# PWM_Controller_SG3525.net
KiCad netlist of a schematic drawn in Altium Designer
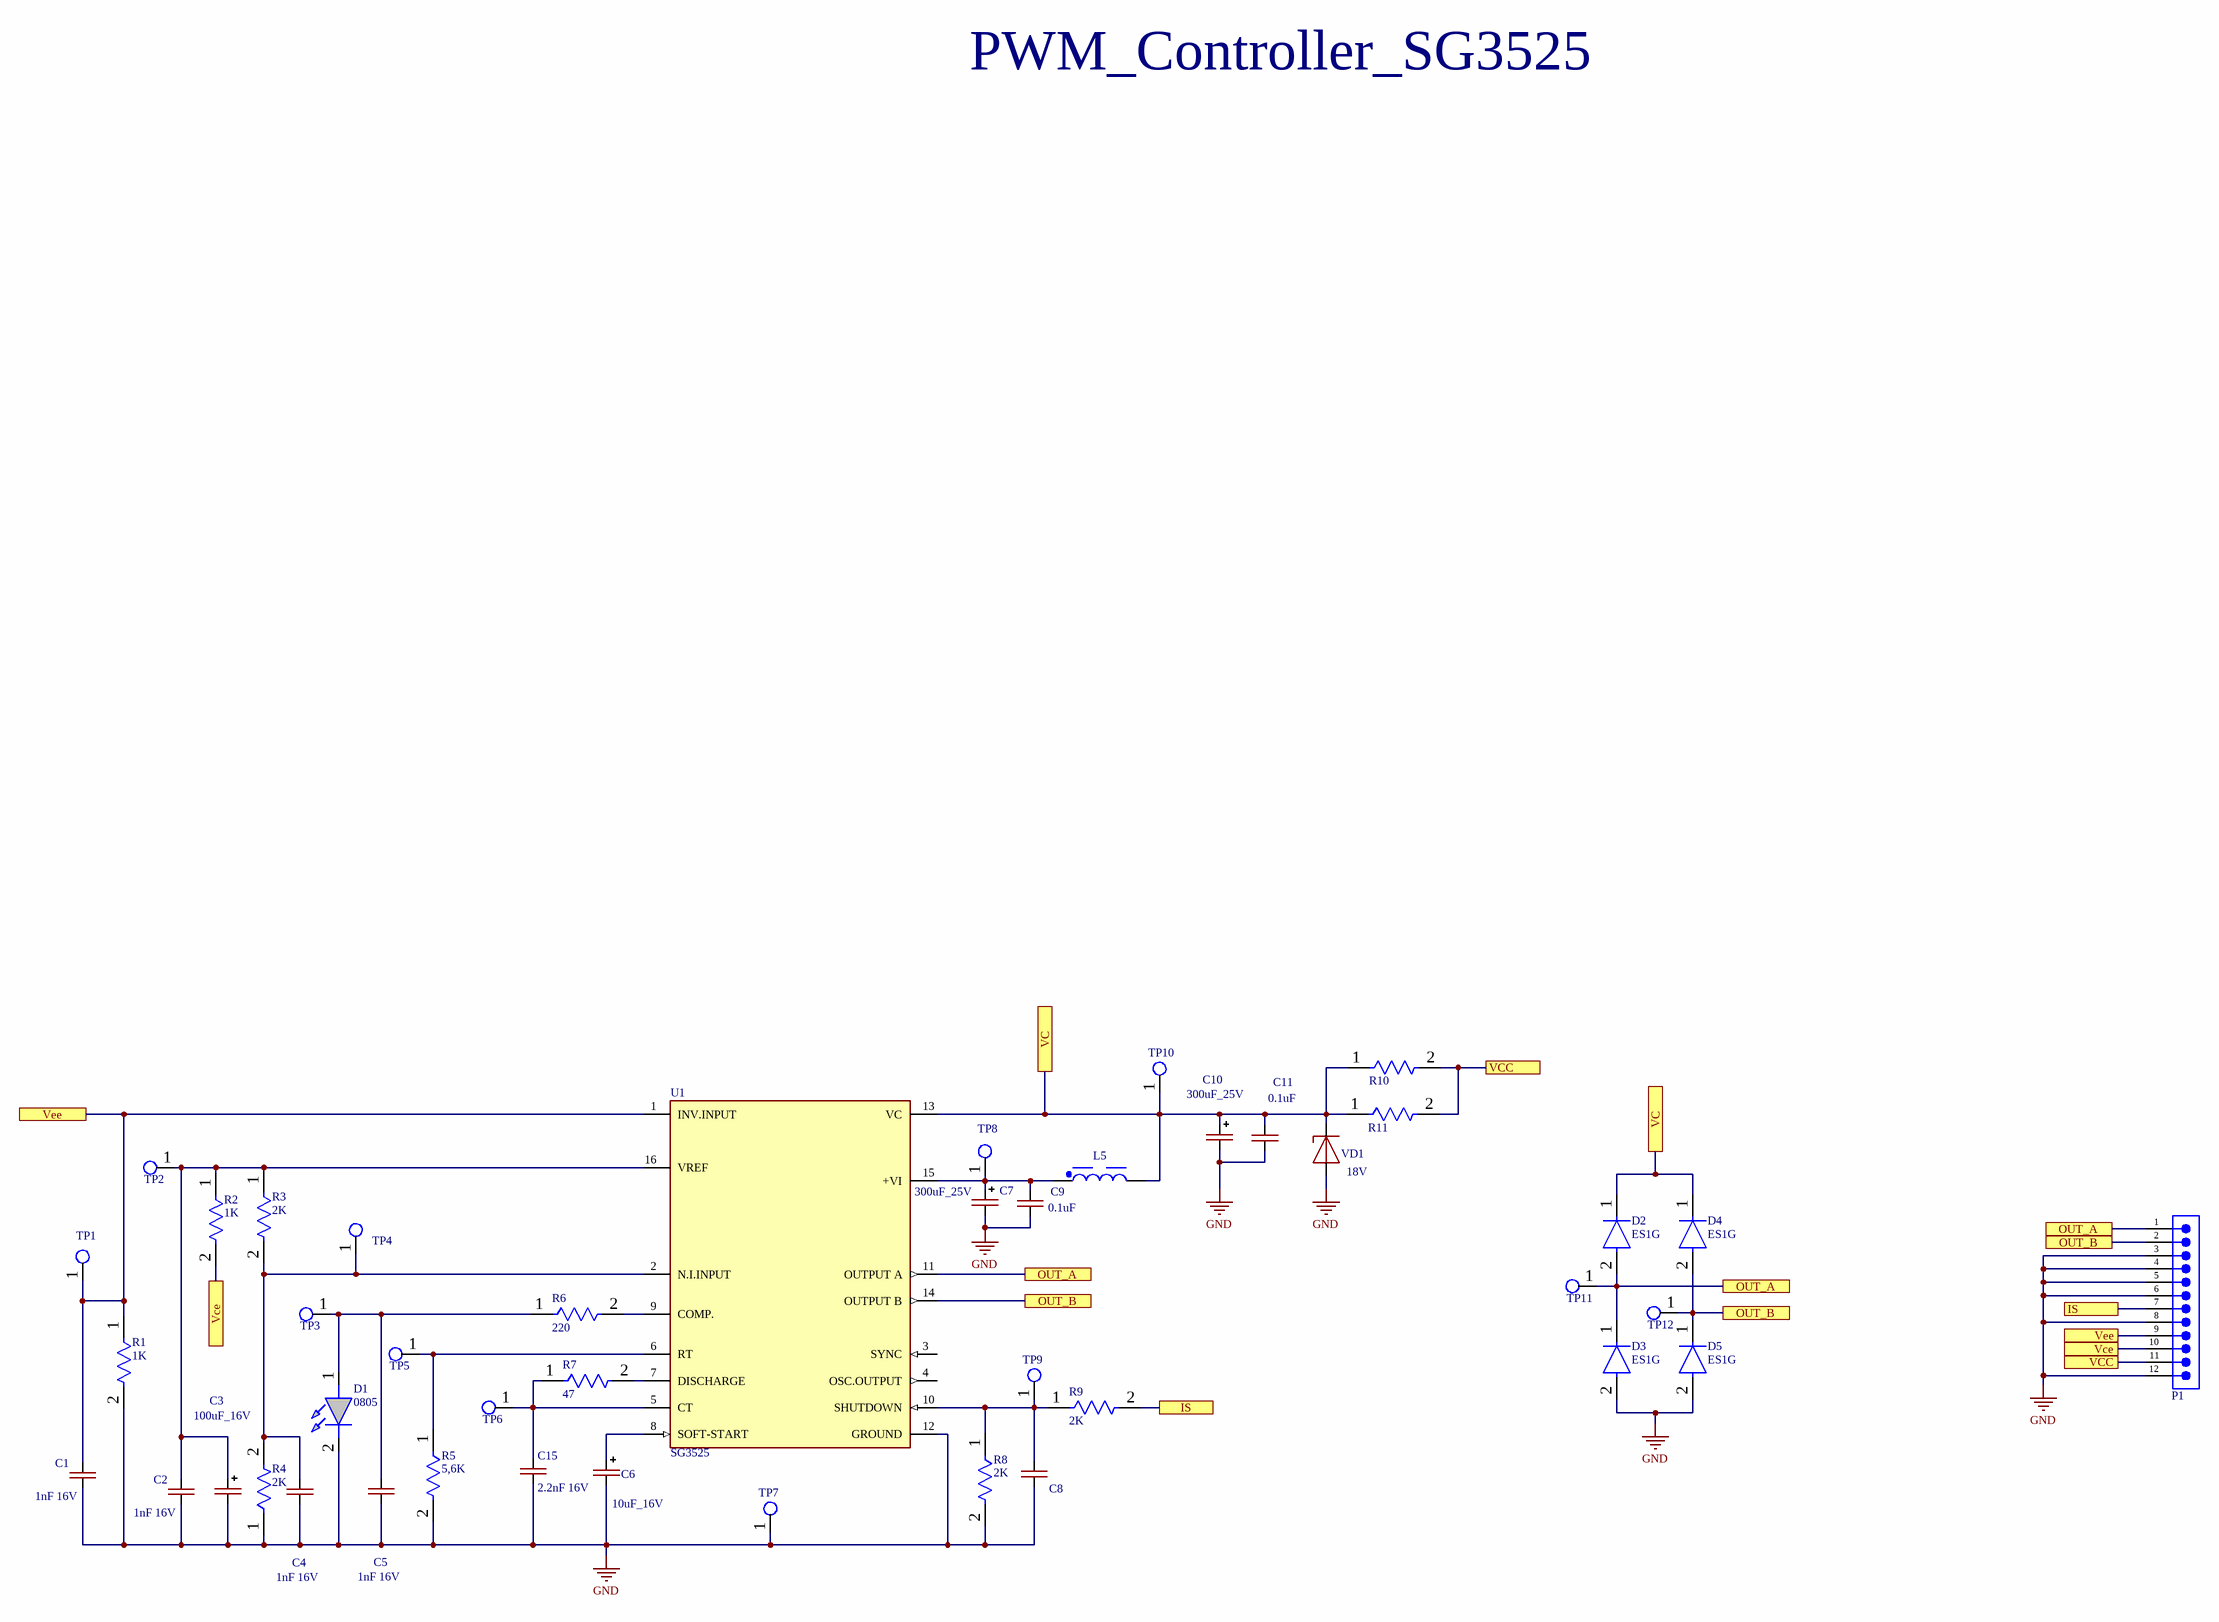
[diagram p0: PWM_Controller_SG3525.SchDoc]

(export (version "E")
  (design (tool "Eeschema 10.0.6"))
  (components
    (comp (ref "C1")
      (value "1nF 16V")
      (footprint "CAP-0805")
      (libsource (lib "PASSIVE_COMPONENTS") (part "CAP-NON-POLAR"))
    )
    (comp (ref "C2")
      (value "1nF 16V")
      (footprint "CAP-0805")
      (libsource (lib "PASSIVE_COMPONENTS") (part "CAP-NON-POLAR"))
    )
    (comp (ref "C3")
      (value "100uF_16V")
      (footprint "CAP-TAN-D")
      (libsource (lib "PASSIVE_COMPONENTS") (part "CAP-POLAR"))
    )
    (comp (ref "C4")
      (value "1nF 16V")
      (footprint "CAP-0805")
      (libsource (lib "PASSIVE_COMPONENTS") (part "CAP-NON-POLAR"))
    )
    (comp (ref "C5")
      (value "1nF 16V")
      (footprint "CAP-0805")
      (libsource (lib "PASSIVE_COMPONENTS") (part "CAP-NON-POLAR"))
    )
    (comp (ref "C6")
      (value "10uF_16V")
      (footprint "CAP-TAN-D")
      (libsource (lib "PASSIVE_COMPONENTS") (part "CAP-POLAR"))
    )
    (comp (ref "C7")
      (value "300uF_25V")
      (footprint "CAP_SMD_Size_G")
      (libsource (lib "PASSIVE_COMPONENTS") (part "CAP_POL_SMD"))
    )
    (comp (ref "C8")
      (value "CAP-NON-POLAR")
      (footprint "CAP-0805")
      (libsource (lib "PASSIVE_COMPONENTS") (part "CAP-NON-POLAR"))
    )
    (comp (ref "C9")
      (value "0.1uF")
      (footprint "CAP-0805")
      (libsource (lib "PASSIVE_COMPONENTS") (part "CAP-NON-POLAR"))
    )
    (comp (ref "C10")
      (value "300uF_25V")
      (footprint "CAP_SMD_Size_G")
      (libsource (lib "PASSIVE_COMPONENTS") (part "CAP_POL_SMD"))
    )
    (comp (ref "C11")
      (value "0.1uF")
      (footprint "CAP-0805")
      (libsource (lib "PASSIVE_COMPONENTS") (part "CAP-NON-POLAR"))
    )
    (comp (ref "C15")
      (value "2.2nF 16V")
      (footprint "CAP-0805")
      (libsource (lib "PASSIVE_COMPONENTS") (part "CAP-NON-POLAR"))
    )
    (comp (ref "D1")
      (value "0805")
      (footprint "LED_RED")
      (description "WURTH ELEKTRONIK - 151031YS06000 - LED, Yellow, Through Hole, T-1 (3mm), 30 mA, 2 V, 590 nm")
      (fields
        (field (name "MANUFACTURER_PART_NUMBER") "151031YS06000")
        (field (name "MOUSER PART NUMBER") "710-151031YS06000")
      )
      (libsource (lib "Optic-LED") (part "LED"))
    )
    (comp (ref "D2")
      (value "ES1G")
      (footprint "FP-403AE-MFG")
      (description "Ultrafast")
      (libsource (lib "Diodes") (part "ES1G"))
    )
    (comp (ref "D3")
      (value "ES1G")
      (footprint "FP-403AE-MFG")
      (description "Ultrafast")
      (libsource (lib "Diodes") (part "ES1G"))
    )
    (comp (ref "D4")
      (value "ES1G")
      (footprint "FP-403AE-MFG")
      (description "Ultrafast")
      (libsource (lib "Diodes") (part "ES1G"))
    )
    (comp (ref "D5")
      (value "ES1G")
      (footprint "FP-403AE-MFG")
      (description "Ultrafast")
      (libsource (lib "Diodes") (part "ES1G"))
    )
    (comp (ref "L5")
      (value "47µH, 1.17A")
      (footprint "WE-PD2_7850")
      (description "WE-PD2 SMT Power Inductor, size 7850, 47µH, 1.17A, 0.18Ω")
      (fields
        (field (name "MANUFACTURER PART NUMBER") "744775147")
        (field (name "MANUFACTURER") "Wurth Elektronik")
      )
      (libsource (lib "WE-PD2 (rev22d)") (part "744775147"))
    )
    (comp (ref "P1")
      (value "61301211021")
      (footprint "61301211021")
      (description "WR-PHD Pin Header, THT, Angled, pitch 2.54mm, 1 Row, 12P")
      (fields (field (name "MANUFACTURER") "Wurth Elektronik"))
      (libsource (lib "Altium_WR-PHD (rev22b)") (part "61301211021"))
    )
    (comp (ref "R1")
      (value "1K")
      (footprint "RES-0805")
      (libsource (lib "PASSIVE_COMPONENTS") (part "RES-CONST"))
    )
    (comp (ref "R2")
      (value "1K")
      (footprint "RES-0805")
      (libsource (lib "PASSIVE_COMPONENTS") (part "RES-CONST"))
    )
    (comp (ref "R3")
      (value "2K")
      (footprint "RES-0805")
      (libsource (lib "PASSIVE_COMPONENTS") (part "RES-CONST"))
    )
    (comp (ref "R4")
      (value "2K")
      (footprint "RES-0805")
      (libsource (lib "PASSIVE_COMPONENTS") (part "RES-CONST"))
    )
    (comp (ref "R5")
      (value "5,6K")
      (footprint "RES-0805")
      (libsource (lib "PASSIVE_COMPONENTS") (part "RES-CONST"))
    )
    (comp (ref "R6")
      (value "220")
      (footprint "RES-0805")
      (libsource (lib "PASSIVE_COMPONENTS") (part "RES-CONST"))
    )
    (comp (ref "R7")
      (value "47")
      (footprint "RES-0805")
      (libsource (lib "PASSIVE_COMPONENTS") (part "RES-CONST"))
    )
    (comp (ref "R8")
      (value "2K")
      (footprint "RES-0805")
      (libsource (lib "PASSIVE_COMPONENTS") (part "RES-CONST"))
    )
    (comp (ref "R9")
      (value "2K")
      (footprint "RES-0805")
      (libsource (lib "PASSIVE_COMPONENTS") (part "RES-CONST"))
    )
    (comp (ref "R10")
      (value "RES_1210")
      (footprint "RES_SMD_1210_IPC_A")
      (libsource (lib "PASSIVE_COMPONENTS") (part "RES_1210"))
    )
    (comp (ref "R11")
      (value "RES_1210")
      (footprint "RES_SMD_1210_IPC_A")
      (libsource (lib "PASSIVE_COMPONENTS") (part "RES_1210"))
    )
    (comp (ref "TP1")
      (value "~")
      (footprint "Test_Point")
      (description "Test_Point")
      (libsource (lib "Connectors") (part "TP_PCB?"))
    )
    (comp (ref "TP2")
      (value "~")
      (footprint "Test_Point")
      (description "Test_Point")
      (libsource (lib "Connectors") (part "TP_PCB?"))
    )
    (comp (ref "TP3")
      (value "~")
      (footprint "Test_Point")
      (description "Test_Point")
      (libsource (lib "Connectors") (part "TP_PCB?"))
    )
    (comp (ref "TP4")
      (value "~")
      (footprint "Test_Point")
      (description "Test_Point")
      (libsource (lib "Connectors") (part "TP_PCB?"))
    )
    (comp (ref "TP5")
      (value "~")
      (footprint "Test_Point")
      (description "Test_Point")
      (libsource (lib "Connectors") (part "TP_PCB?"))
    )
    (comp (ref "TP6")
      (value "~")
      (footprint "Test_Point")
      (description "Test_Point")
      (libsource (lib "Connectors") (part "TP_PCB?"))
    )
    (comp (ref "TP7")
      (value "~")
      (footprint "Test_Point")
      (description "Test_Point")
      (libsource (lib "Connectors") (part "TP_PCB?"))
    )
    (comp (ref "TP8")
      (value "~")
      (footprint "Test_Point")
      (description "Test_Point")
      (libsource (lib "Connectors") (part "TP_PCB?"))
    )
    (comp (ref "TP9")
      (value "~")
      (footprint "Test_Point")
      (description "Test_Point")
      (libsource (lib "Connectors") (part "TP_PCB?"))
    )
    (comp (ref "TP10")
      (value "~")
      (footprint "Test_Point")
      (description "Test_Point")
      (libsource (lib "Connectors") (part "TP_PCB?"))
    )
    (comp (ref "TP11")
      (value "~")
      (footprint "Test_Point")
      (description "Test_Point")
      (libsource (lib "Connectors") (part "TP_PCB?"))
    )
    (comp (ref "TP12")
      (value "~")
      (footprint "Test_Point")
      (description "Test_Point")
      (libsource (lib "Connectors") (part "TP_PCB?"))
    )
    (comp (ref "U1")
      (value "SG3525")
      (footprint "SOIC-16-L")
      (libsource (lib "Integrated_Circuts") (part "SG3525"))
    )
    (comp (ref "VD1") (value "18V") (footprint "DO-017AA") (libsource (lib "Diodes") (part "ZENER")))
  )
  (nets
    (net (code "1") (name "/IS") (class "Default")
      (node (ref "P1") (pin "7") (pinfunction "7_7") (pintype "passive"))
      (node (ref "R9") (pin "2") (pinfunction "2_2") (pintype "passive"))
    )
    (net (code "2") (name "/OUT_A") (class "Default")
      (node (ref "D2") (pin "2") (pinfunction "A_2") (pintype "passive"))
      (node (ref "D3") (pin "1") (pinfunction "C_1") (pintype "passive"))
      (node (ref "P1") (pin "1") (pinfunction "1_1") (pintype "passive"))
      (node (ref "TP11") (pin "1") (pinfunction "G9_1") (pintype "passive"))
      (node (ref "U1") (pin "11") (pinfunction "OUTPUT_A_11") (pintype "output"))
    )
    (net (code "3") (name "/OUT_B") (class "Default")
      (node (ref "D4") (pin "2") (pinfunction "A_2") (pintype "passive"))
      (node (ref "D5") (pin "1") (pinfunction "C_1") (pintype "passive"))
      (node (ref "P1") (pin "2") (pinfunction "2_2") (pintype "passive"))
      (node (ref "TP12") (pin "1") (pinfunction "G9_1") (pintype "passive"))
      (node (ref "U1") (pin "14") (pinfunction "OUTPUT_B_14") (pintype "output"))
    )
    (net (code "4") (name "/VC") (class "Default")
      (node (ref "C10") (pin "1") (pinfunction "+_1") (pintype "passive"))
      (node (ref "C11") (pin "2") (pinfunction "2_2") (pintype "passive"))
      (node (ref "D2") (pin "1") (pinfunction "C_1") (pintype "passive"))
      (node (ref "D4") (pin "1") (pinfunction "C_1") (pintype "passive"))
      (node (ref "L5") (pin "2") (pinfunction "2_2") (pintype "passive"))
      (node (ref "R10") (pin "1") (pinfunction "1_1") (pintype "passive"))
      (node (ref "R11") (pin "1") (pinfunction "1_1") (pintype "passive"))
      (node (ref "TP10") (pin "1") (pinfunction "G9_1") (pintype "passive"))
      (node (ref "U1") (pin "13") (pinfunction "VC_13") (pintype "power_in"))
      (node (ref "VD1") (pin "1") (pinfunction "C_1") (pintype "passive"))
    )
    (net (code "5") (name "/VCC") (class "Default")
      (node (ref "P1") (pin "11") (pinfunction "11_11") (pintype "passive"))
      (node (ref "R10") (pin "2") (pinfunction "2_2") (pintype "passive"))
      (node (ref "R11") (pin "2") (pinfunction "2_2") (pintype "passive"))
    )
    (net (code "6") (name "/Vce") (class "Default")
      (node (ref "P1") (pin "10") (pinfunction "10_10") (pintype "passive"))
      (node (ref "R2") (pin "2") (pinfunction "2_2") (pintype "passive"))
    )
    (net (code "7") (name "/Vee") (class "Default")
      (node (ref "C1") (pin "2") (pinfunction "2_2") (pintype "passive"))
      (node (ref "P1") (pin "9") (pinfunction "9_9") (pintype "passive"))
      (node (ref "R1") (pin "1") (pinfunction "1_1") (pintype "passive"))
      (node (ref "TP1") (pin "1") (pinfunction "G9_1") (pintype "passive"))
      (node (ref "U1") (pin "1") (pinfunction "INV.INPUT_1") (pintype "tri_state"))
    )
    (net (code "8") (name "GND") (class "Default")
      (node (ref "C1") (pin "1") (pinfunction "1_1") (pintype "passive"))
      (node (ref "C10") (pin "2") (pinfunction "-_2") (pintype "passive"))
      (node (ref "C11") (pin "1") (pinfunction "1_1") (pintype "passive"))
      (node (ref "C15") (pin "1") (pinfunction "1_1") (pintype "passive"))
      (node (ref "C2") (pin "1") (pinfunction "1_1") (pintype "passive"))
      (node (ref "C3") (pin "2") (pinfunction "-_2") (pintype "passive"))
      (node (ref "C4") (pin "1") (pinfunction "1_1") (pintype "passive"))
      (node (ref "C5") (pin "1") (pinfunction "1_1") (pintype "passive"))
      (node (ref "C6") (pin "2") (pinfunction "-_2") (pintype "passive"))
      (node (ref "C7") (pin "2") (pinfunction "-_2") (pintype "passive"))
      (node (ref "C8") (pin "1") (pinfunction "1_1") (pintype "passive"))
      (node (ref "C9") (pin "1") (pinfunction "1_1") (pintype "passive"))
      (node (ref "D1") (pin "2") (pinfunction "K_2") (pintype "passive"))
      (node (ref "D3") (pin "2") (pinfunction "A_2") (pintype "passive"))
      (node (ref "D5") (pin "2") (pinfunction "A_2") (pintype "passive"))
      (node (ref "P1") (pin "12") (pinfunction "12_12") (pintype "passive"))
      (node (ref "P1") (pin "3") (pinfunction "3_3") (pintype "passive"))
      (node (ref "P1") (pin "4") (pinfunction "4_4") (pintype "passive"))
      (node (ref "P1") (pin "5") (pinfunction "5_5") (pintype "passive"))
      (node (ref "P1") (pin "6") (pinfunction "6_6") (pintype "passive"))
      (node (ref "P1") (pin "8") (pinfunction "8_8") (pintype "passive"))
      (node (ref "R1") (pin "2") (pinfunction "2_2") (pintype "passive"))
      (node (ref "R4") (pin "1") (pinfunction "1_1") (pintype "passive"))
      (node (ref "R5") (pin "2") (pinfunction "2_2") (pintype "passive"))
      (node (ref "R8") (pin "2") (pinfunction "2_2") (pintype "passive"))
      (node (ref "TP7") (pin "1") (pinfunction "G9_1") (pintype "passive"))
      (node (ref "U1") (pin "12") (pinfunction "GROUND_12") (pintype "power_in"))
      (node (ref "VD1") (pin "2") (pinfunction "A_2") (pintype "passive"))
    )
    (net (code "9") (name "Net-(C3-+)") (class "Default")
      (node (ref "C2") (pin "2") (pinfunction "2_2") (pintype "passive"))
      (node (ref "C3") (pin "1") (pinfunction "+_1") (pintype "passive"))
      (node (ref "R2") (pin "1") (pinfunction "1_1") (pintype "passive"))
      (node (ref "R3") (pin "1") (pinfunction "1_1") (pintype "passive"))
      (node (ref "TP2") (pin "1") (pinfunction "G9_1") (pintype "passive"))
      (node (ref "U1") (pin "16") (pinfunction "VREF_16") (pintype "passive"))
    )
    (net (code "10") (name "Net-(C6-+)") (class "Default")
      (node (ref "C6") (pin "1") (pinfunction "+_1") (pintype "passive"))
      (node (ref "U1") (pin "8") (pinfunction "SOFT-START_8") (pintype "input"))
    )
    (net (code "11") (name "Net-(C7-+)") (class "Default")
      (node (ref "C7") (pin "1") (pinfunction "+_1") (pintype "passive"))
      (node (ref "C9") (pin "2") (pinfunction "2_2") (pintype "passive"))
      (node (ref "L5") (pin "1") (pinfunction "1_1") (pintype "passive"))
      (node (ref "TP8") (pin "1") (pinfunction "G9_1") (pintype "passive"))
      (node (ref "U1") (pin "15") (pinfunction "+VI_15") (pintype "power_in"))
    )
    (net (code "12") (name "Net-(D1-A)") (class "Default")
      (node (ref "C5") (pin "2") (pinfunction "2_2") (pintype "passive"))
      (node (ref "D1") (pin "1") (pinfunction "A_1") (pintype "passive"))
      (node (ref "R6") (pin "1") (pinfunction "1_1") (pintype "passive"))
      (node (ref "TP3") (pin "1") (pinfunction "G9_1") (pintype "passive"))
    )
    (net (code "13") (name "Net-(TP4-G9)") (class "Default")
      (node (ref "C4") (pin "2") (pinfunction "2_2") (pintype "passive"))
      (node (ref "R3") (pin "2") (pinfunction "2_2") (pintype "passive"))
      (node (ref "R4") (pin "2") (pinfunction "2_2") (pintype "passive"))
      (node (ref "TP4") (pin "1") (pinfunction "G9_1") (pintype "passive"))
      (node (ref "U1") (pin "2") (pinfunction "N.I.INPUT_2") (pintype "tri_state"))
    )
    (net (code "14") (name "Net-(TP5-G9)") (class "Default")
      (node (ref "R5") (pin "1") (pinfunction "1_1") (pintype "passive"))
      (node (ref "TP5") (pin "1") (pinfunction "G9_1") (pintype "passive"))
      (node (ref "U1") (pin "6") (pinfunction "RT_6") (pintype "passive"))
    )
    (net (code "15") (name "Net-(TP6-G9)") (class "Default")
      (node (ref "C15") (pin "2") (pinfunction "2_2") (pintype "passive"))
      (node (ref "R7") (pin "1") (pinfunction "1_1") (pintype "passive"))
      (node (ref "TP6") (pin "1") (pinfunction "G9_1") (pintype "passive"))
      (node (ref "U1") (pin "5") (pinfunction "CT_5") (pintype "passive"))
    )
    (net (code "16") (name "Net-(TP9-G9)") (class "Default")
      (node (ref "C8") (pin "2") (pinfunction "2_2") (pintype "passive"))
      (node (ref "R8") (pin "1") (pinfunction "1_1") (pintype "passive"))
      (node (ref "R9") (pin "1") (pinfunction "1_1") (pintype "passive"))
      (node (ref "TP9") (pin "1") (pinfunction "G9_1") (pintype "passive"))
      (node (ref "U1") (pin "10") (pinfunction "SHUTDOWN_10") (pintype "input"))
    )
    (net (code "17") (name "Net-(U1-COMP.)") (class "Default")
      (node (ref "R6") (pin "2") (pinfunction "2_2") (pintype "passive"))
      (node (ref "U1") (pin "9") (pinfunction "COMP._9") (pintype "passive"))
    )
    (net (code "18") (name "Net-(U1-DISCHARGE)") (class "Default")
      (node (ref "R7") (pin "2") (pinfunction "2_2") (pintype "passive"))
      (node (ref "U1") (pin "7") (pinfunction "DISCHARGE_7") (pintype "passive"))
    )
    (net (code "19") (name "unconnected-(U1-OSC.OUTPUT-Pad4)") (class "Default")
      (node (ref "U1") (pin "4") (pinfunction "OSC.OUTPUT_4") (pintype "output"))
    )
    (net (code "20") (name "unconnected-(U1-SYNC-Pad3)") (class "Default")
      (node (ref "U1") (pin "3") (pinfunction "SYNC_3") (pintype "input"))
    )
  )
)
